# Photodiodes.net
KiCad netlist of a schematic drawn in Altium Designer
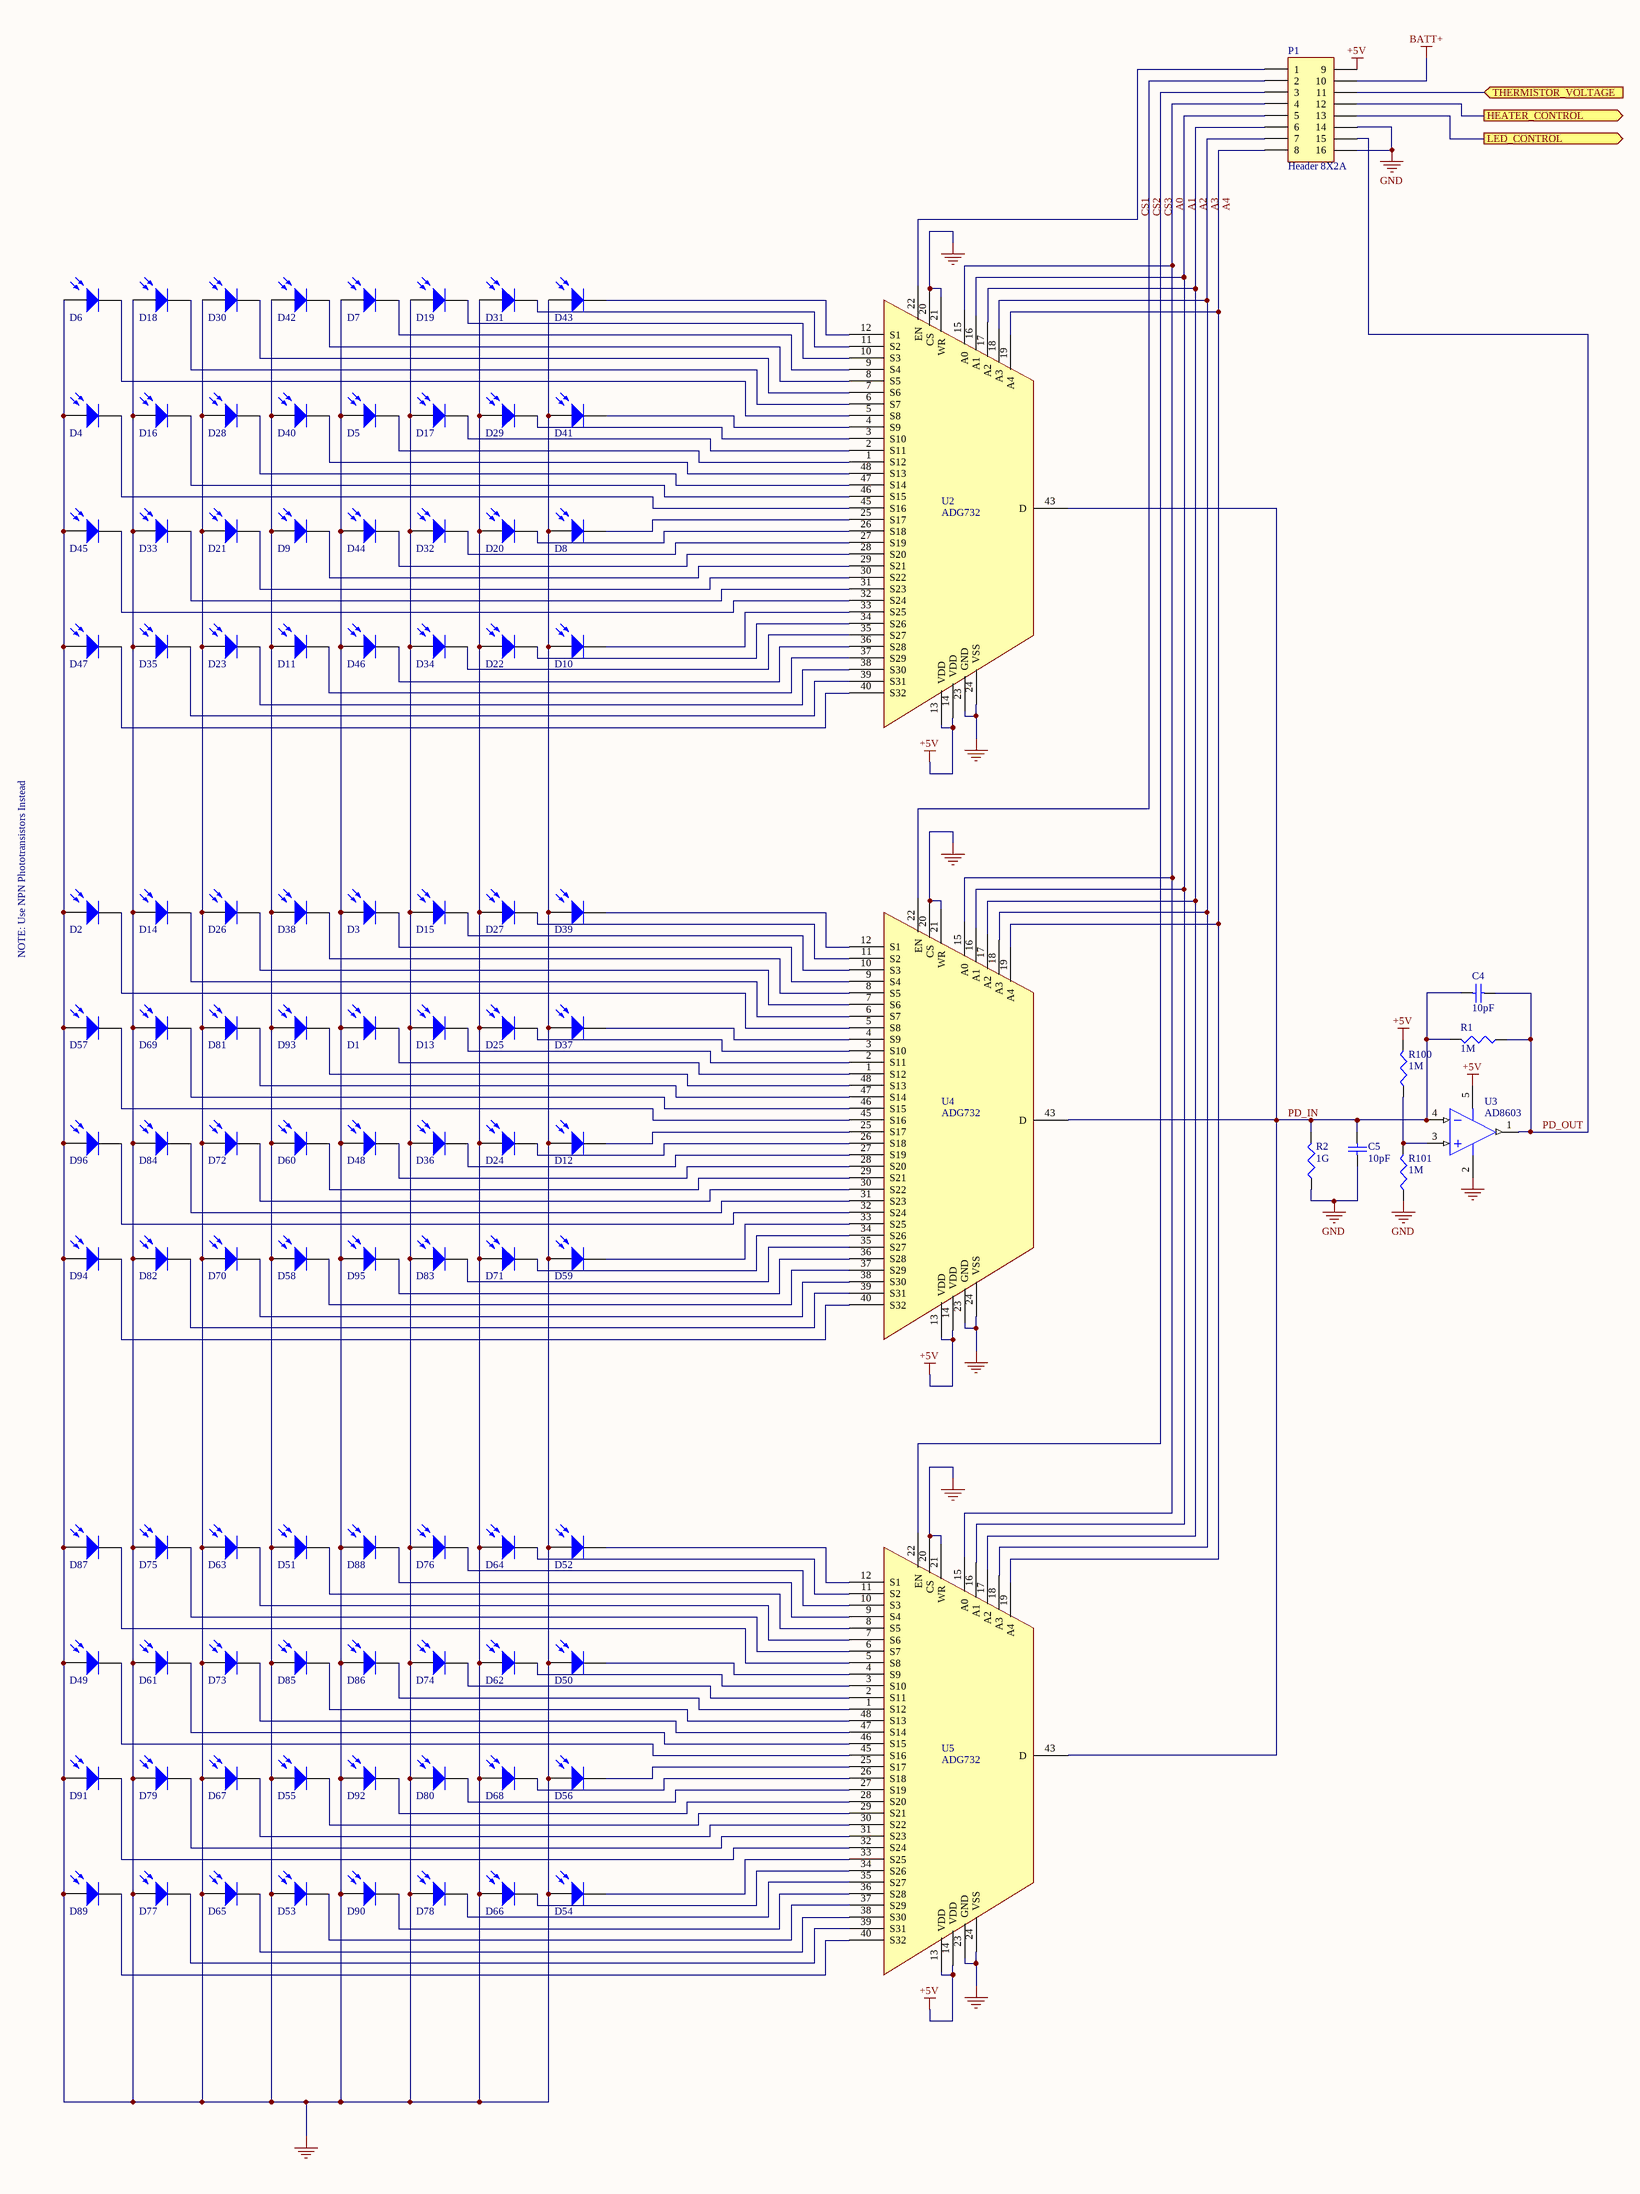
[diagram p0: Photodiodes.SchDoc]

(export (version "E")
  (design (tool "Eeschema 10.0.6"))
  (components
    (comp (ref "C4")
      (value "10pF")
      (footprint "CAPC3216L")
      (description "Capacitor (Semiconductor SIM Model)")
      (fields (field (name "Comment") "Cap Semi"))
      (libsource (lib "Miscellaneous Devices") (part "Cap Semi"))
    )
    (comp (ref "C5")
      (value "10pF")
      (footprint "CAPC3216L")
      (description "Capacitor (Semiconductor SIM Model)")
      (fields (field (name "Comment") "Cap Semi"))
      (libsource (lib "Miscellaneous Devices") (part "Cap Semi"))
    )
    (comp (ref "D1")
      (value "Photo Sen")
      (footprint "CAPC2012L")
      (description "Photosensitive Diode")
      (libsource (lib "Miscellaneous Devices") (part "Photo Sen"))
    )
    (comp (ref "D2")
      (value "Photo Sen")
      (footprint "CAPC2012L")
      (description "Photosensitive Diode")
      (libsource (lib "Miscellaneous Devices") (part "Photo Sen"))
    )
    (comp (ref "D3")
      (value "Photo Sen")
      (footprint "CAPC2012L")
      (description "Photosensitive Diode")
      (libsource (lib "Miscellaneous Devices") (part "Photo Sen"))
    )
    (comp (ref "D4")
      (value "Photo Sen")
      (footprint "CAPC2012L")
      (description "Photosensitive Diode")
      (libsource (lib "Miscellaneous Devices") (part "Photo Sen"))
    )
    (comp (ref "D5")
      (value "Photo Sen")
      (footprint "CAPC2012L")
      (description "Photosensitive Diode")
      (libsource (lib "Miscellaneous Devices") (part "Photo Sen"))
    )
    (comp (ref "D6")
      (value "Photo Sen")
      (footprint "CAPC2012L")
      (description "Photosensitive Diode")
      (libsource (lib "Miscellaneous Devices") (part "Photo Sen"))
    )
    (comp (ref "D7")
      (value "Photo Sen")
      (footprint "CAPC2012L")
      (description "Photosensitive Diode")
      (libsource (lib "Miscellaneous Devices") (part "Photo Sen"))
    )
    (comp (ref "D8")
      (value "Photo Sen")
      (footprint "CAPC2012L")
      (description "Photosensitive Diode")
      (libsource (lib "Miscellaneous Devices") (part "Photo Sen"))
    )
    (comp (ref "D9")
      (value "Photo Sen")
      (footprint "CAPC2012L")
      (description "Photosensitive Diode")
      (libsource (lib "Miscellaneous Devices") (part "Photo Sen"))
    )
    (comp (ref "D10")
      (value "Photo Sen")
      (footprint "CAPC2012L")
      (description "Photosensitive Diode")
      (libsource (lib "Miscellaneous Devices") (part "Photo Sen"))
    )
    (comp (ref "D11")
      (value "Photo Sen")
      (footprint "CAPC2012L")
      (description "Photosensitive Diode")
      (libsource (lib "Miscellaneous Devices") (part "Photo Sen"))
    )
    (comp (ref "D12")
      (value "Photo Sen")
      (footprint "CAPC2012L")
      (description "Photosensitive Diode")
      (libsource (lib "Miscellaneous Devices") (part "Photo Sen"))
    )
    (comp (ref "D13")
      (value "Photo Sen")
      (footprint "CAPC2012L")
      (description "Photosensitive Diode")
      (libsource (lib "Miscellaneous Devices") (part "Photo Sen"))
    )
    (comp (ref "D14")
      (value "Photo Sen")
      (footprint "CAPC2012L")
      (description "Photosensitive Diode")
      (libsource (lib "Miscellaneous Devices") (part "Photo Sen"))
    )
    (comp (ref "D15")
      (value "Photo Sen")
      (footprint "CAPC2012L")
      (description "Photosensitive Diode")
      (libsource (lib "Miscellaneous Devices") (part "Photo Sen"))
    )
    (comp (ref "D16")
      (value "Photo Sen")
      (footprint "CAPC2012L")
      (description "Photosensitive Diode")
      (libsource (lib "Miscellaneous Devices") (part "Photo Sen"))
    )
    (comp (ref "D17")
      (value "Photo Sen")
      (footprint "CAPC2012L")
      (description "Photosensitive Diode")
      (libsource (lib "Miscellaneous Devices") (part "Photo Sen"))
    )
    (comp (ref "D18")
      (value "Photo Sen")
      (footprint "CAPC2012L")
      (description "Photosensitive Diode")
      (libsource (lib "Miscellaneous Devices") (part "Photo Sen"))
    )
    (comp (ref "D19")
      (value "Photo Sen")
      (footprint "CAPC2012L")
      (description "Photosensitive Diode")
      (libsource (lib "Miscellaneous Devices") (part "Photo Sen"))
    )
    (comp (ref "D20")
      (value "Photo Sen")
      (footprint "CAPC2012L")
      (description "Photosensitive Diode")
      (libsource (lib "Miscellaneous Devices") (part "Photo Sen"))
    )
    (comp (ref "D21")
      (value "Photo Sen")
      (footprint "CAPC2012L")
      (description "Photosensitive Diode")
      (libsource (lib "Miscellaneous Devices") (part "Photo Sen"))
    )
    (comp (ref "D22")
      (value "Photo Sen")
      (footprint "CAPC2012L")
      (description "Photosensitive Diode")
      (libsource (lib "Miscellaneous Devices") (part "Photo Sen"))
    )
    (comp (ref "D23")
      (value "Photo Sen")
      (footprint "CAPC2012L")
      (description "Photosensitive Diode")
      (libsource (lib "Miscellaneous Devices") (part "Photo Sen"))
    )
    (comp (ref "D24")
      (value "Photo Sen")
      (footprint "CAPC2012L")
      (description "Photosensitive Diode")
      (libsource (lib "Miscellaneous Devices") (part "Photo Sen"))
    )
    (comp (ref "D25")
      (value "Photo Sen")
      (footprint "CAPC2012L")
      (description "Photosensitive Diode")
      (libsource (lib "Miscellaneous Devices") (part "Photo Sen"))
    )
    (comp (ref "D26")
      (value "Photo Sen")
      (footprint "CAPC2012L")
      (description "Photosensitive Diode")
      (libsource (lib "Miscellaneous Devices") (part "Photo Sen"))
    )
    (comp (ref "D27")
      (value "Photo Sen")
      (footprint "CAPC2012L")
      (description "Photosensitive Diode")
      (libsource (lib "Miscellaneous Devices") (part "Photo Sen"))
    )
    (comp (ref "D28")
      (value "Photo Sen")
      (footprint "CAPC2012L")
      (description "Photosensitive Diode")
      (libsource (lib "Miscellaneous Devices") (part "Photo Sen"))
    )
    (comp (ref "D29")
      (value "Photo Sen")
      (footprint "CAPC2012L")
      (description "Photosensitive Diode")
      (libsource (lib "Miscellaneous Devices") (part "Photo Sen"))
    )
    (comp (ref "D30")
      (value "Photo Sen")
      (footprint "CAPC2012L")
      (description "Photosensitive Diode")
      (libsource (lib "Miscellaneous Devices") (part "Photo Sen"))
    )
    (comp (ref "D31")
      (value "Photo Sen")
      (footprint "CAPC2012L")
      (description "Photosensitive Diode")
      (libsource (lib "Miscellaneous Devices") (part "Photo Sen"))
    )
    (comp (ref "D32")
      (value "Photo Sen")
      (footprint "CAPC2012L")
      (description "Photosensitive Diode")
      (libsource (lib "Miscellaneous Devices") (part "Photo Sen"))
    )
    (comp (ref "D33")
      (value "Photo Sen")
      (footprint "CAPC2012L")
      (description "Photosensitive Diode")
      (libsource (lib "Miscellaneous Devices") (part "Photo Sen"))
    )
    (comp (ref "D34")
      (value "Photo Sen")
      (footprint "CAPC2012L")
      (description "Photosensitive Diode")
      (libsource (lib "Miscellaneous Devices") (part "Photo Sen"))
    )
    (comp (ref "D35")
      (value "Photo Sen")
      (footprint "CAPC2012L")
      (description "Photosensitive Diode")
      (libsource (lib "Miscellaneous Devices") (part "Photo Sen"))
    )
    (comp (ref "D36")
      (value "Photo Sen")
      (footprint "CAPC2012L")
      (description "Photosensitive Diode")
      (libsource (lib "Miscellaneous Devices") (part "Photo Sen"))
    )
    (comp (ref "D37")
      (value "Photo Sen")
      (footprint "CAPC2012L")
      (description "Photosensitive Diode")
      (libsource (lib "Miscellaneous Devices") (part "Photo Sen"))
    )
    (comp (ref "D38")
      (value "Photo Sen")
      (footprint "CAPC2012L")
      (description "Photosensitive Diode")
      (libsource (lib "Miscellaneous Devices") (part "Photo Sen"))
    )
    (comp (ref "D39")
      (value "Photo Sen")
      (footprint "CAPC2012L")
      (description "Photosensitive Diode")
      (libsource (lib "Miscellaneous Devices") (part "Photo Sen"))
    )
    (comp (ref "D40")
      (value "Photo Sen")
      (footprint "CAPC2012L")
      (description "Photosensitive Diode")
      (libsource (lib "Miscellaneous Devices") (part "Photo Sen"))
    )
    (comp (ref "D41")
      (value "Photo Sen")
      (footprint "CAPC2012L")
      (description "Photosensitive Diode")
      (libsource (lib "Miscellaneous Devices") (part "Photo Sen"))
    )
    (comp (ref "D42")
      (value "Photo Sen")
      (footprint "CAPC2012L")
      (description "Photosensitive Diode")
      (libsource (lib "Miscellaneous Devices") (part "Photo Sen"))
    )
    (comp (ref "D43")
      (value "Photo Sen")
      (footprint "CAPC2012L")
      (description "Photosensitive Diode")
      (libsource (lib "Miscellaneous Devices") (part "Photo Sen"))
    )
    (comp (ref "D44")
      (value "Photo Sen")
      (footprint "CAPC2012L")
      (description "Photosensitive Diode")
      (libsource (lib "Miscellaneous Devices") (part "Photo Sen"))
    )
    (comp (ref "D45")
      (value "Photo Sen")
      (footprint "CAPC2012L")
      (description "Photosensitive Diode")
      (libsource (lib "Miscellaneous Devices") (part "Photo Sen"))
    )
    (comp (ref "D46")
      (value "Photo Sen")
      (footprint "CAPC2012L")
      (description "Photosensitive Diode")
      (libsource (lib "Miscellaneous Devices") (part "Photo Sen"))
    )
    (comp (ref "D47")
      (value "Photo Sen")
      (footprint "CAPC2012L")
      (description "Photosensitive Diode")
      (libsource (lib "Miscellaneous Devices") (part "Photo Sen"))
    )
    (comp (ref "D48")
      (value "Photo Sen")
      (footprint "CAPC2012L")
      (description "Photosensitive Diode")
      (libsource (lib "Miscellaneous Devices") (part "Photo Sen"))
    )
    (comp (ref "D49")
      (value "Photo Sen")
      (footprint "CAPC2012L")
      (description "Photosensitive Diode")
      (libsource (lib "Miscellaneous Devices") (part "Photo Sen"))
    )
    (comp (ref "D50")
      (value "Photo Sen")
      (footprint "CAPC2012L")
      (description "Photosensitive Diode")
      (libsource (lib "Miscellaneous Devices") (part "Photo Sen"))
    )
    (comp (ref "D51")
      (value "Photo Sen")
      (footprint "CAPC2012L")
      (description "Photosensitive Diode")
      (libsource (lib "Miscellaneous Devices") (part "Photo Sen"))
    )
    (comp (ref "D52")
      (value "Photo Sen")
      (footprint "CAPC2012L")
      (description "Photosensitive Diode")
      (libsource (lib "Miscellaneous Devices") (part "Photo Sen"))
    )
    (comp (ref "D53")
      (value "Photo Sen")
      (footprint "CAPC2012L")
      (description "Photosensitive Diode")
      (libsource (lib "Miscellaneous Devices") (part "Photo Sen"))
    )
    (comp (ref "D54")
      (value "Photo Sen")
      (footprint "CAPC2012L")
      (description "Photosensitive Diode")
      (libsource (lib "Miscellaneous Devices") (part "Photo Sen"))
    )
    (comp (ref "D55")
      (value "Photo Sen")
      (footprint "CAPC2012L")
      (description "Photosensitive Diode")
      (libsource (lib "Miscellaneous Devices") (part "Photo Sen"))
    )
    (comp (ref "D56")
      (value "Photo Sen")
      (footprint "CAPC2012L")
      (description "Photosensitive Diode")
      (libsource (lib "Miscellaneous Devices") (part "Photo Sen"))
    )
    (comp (ref "D57")
      (value "Photo Sen")
      (footprint "CAPC2012L")
      (description "Photosensitive Diode")
      (libsource (lib "Miscellaneous Devices") (part "Photo Sen"))
    )
    (comp (ref "D58")
      (value "Photo Sen")
      (footprint "CAPC2012L")
      (description "Photosensitive Diode")
      (libsource (lib "Miscellaneous Devices") (part "Photo Sen"))
    )
    (comp (ref "D59")
      (value "Photo Sen")
      (footprint "CAPC2012L")
      (description "Photosensitive Diode")
      (libsource (lib "Miscellaneous Devices") (part "Photo Sen"))
    )
    (comp (ref "D60")
      (value "Photo Sen")
      (footprint "CAPC2012L")
      (description "Photosensitive Diode")
      (libsource (lib "Miscellaneous Devices") (part "Photo Sen"))
    )
    (comp (ref "D61")
      (value "Photo Sen")
      (footprint "CAPC2012L")
      (description "Photosensitive Diode")
      (libsource (lib "Miscellaneous Devices") (part "Photo Sen"))
    )
    (comp (ref "D62")
      (value "Photo Sen")
      (footprint "CAPC2012L")
      (description "Photosensitive Diode")
      (libsource (lib "Miscellaneous Devices") (part "Photo Sen"))
    )
    (comp (ref "D63")
      (value "Photo Sen")
      (footprint "CAPC2012L")
      (description "Photosensitive Diode")
      (libsource (lib "Miscellaneous Devices") (part "Photo Sen"))
    )
    (comp (ref "D64")
      (value "Photo Sen")
      (footprint "CAPC2012L")
      (description "Photosensitive Diode")
      (libsource (lib "Miscellaneous Devices") (part "Photo Sen"))
    )
    (comp (ref "D65")
      (value "Photo Sen")
      (footprint "CAPC2012L")
      (description "Photosensitive Diode")
      (libsource (lib "Miscellaneous Devices") (part "Photo Sen"))
    )
    (comp (ref "D66")
      (value "Photo Sen")
      (footprint "CAPC2012L")
      (description "Photosensitive Diode")
      (libsource (lib "Miscellaneous Devices") (part "Photo Sen"))
    )
    (comp (ref "D67")
      (value "Photo Sen")
      (footprint "CAPC2012L")
      (description "Photosensitive Diode")
      (libsource (lib "Miscellaneous Devices") (part "Photo Sen"))
    )
    (comp (ref "D68")
      (value "Photo Sen")
      (footprint "CAPC2012L")
      (description "Photosensitive Diode")
      (libsource (lib "Miscellaneous Devices") (part "Photo Sen"))
    )
    (comp (ref "D69")
      (value "Photo Sen")
      (footprint "CAPC2012L")
      (description "Photosensitive Diode")
      (libsource (lib "Miscellaneous Devices") (part "Photo Sen"))
    )
    (comp (ref "D70")
      (value "Photo Sen")
      (footprint "CAPC2012L")
      (description "Photosensitive Diode")
      (libsource (lib "Miscellaneous Devices") (part "Photo Sen"))
    )
    (comp (ref "D71")
      (value "Photo Sen")
      (footprint "CAPC2012L")
      (description "Photosensitive Diode")
      (libsource (lib "Miscellaneous Devices") (part "Photo Sen"))
    )
    (comp (ref "D72")
      (value "Photo Sen")
      (footprint "CAPC2012L")
      (description "Photosensitive Diode")
      (libsource (lib "Miscellaneous Devices") (part "Photo Sen"))
    )
    (comp (ref "D73")
      (value "Photo Sen")
      (footprint "CAPC2012L")
      (description "Photosensitive Diode")
      (libsource (lib "Miscellaneous Devices") (part "Photo Sen"))
    )
    (comp (ref "D74")
      (value "Photo Sen")
      (footprint "CAPC2012L")
      (description "Photosensitive Diode")
      (libsource (lib "Miscellaneous Devices") (part "Photo Sen"))
    )
    (comp (ref "D75")
      (value "Photo Sen")
      (footprint "CAPC2012L")
      (description "Photosensitive Diode")
      (libsource (lib "Miscellaneous Devices") (part "Photo Sen"))
    )
    (comp (ref "D76")
      (value "Photo Sen")
      (footprint "CAPC2012L")
      (description "Photosensitive Diode")
      (libsource (lib "Miscellaneous Devices") (part "Photo Sen"))
    )
    (comp (ref "D77")
      (value "Photo Sen")
      (footprint "CAPC2012L")
      (description "Photosensitive Diode")
      (libsource (lib "Miscellaneous Devices") (part "Photo Sen"))
    )
    (comp (ref "D78")
      (value "Photo Sen")
      (footprint "CAPC2012L")
      (description "Photosensitive Diode")
      (libsource (lib "Miscellaneous Devices") (part "Photo Sen"))
    )
    (comp (ref "D79")
      (value "Photo Sen")
      (footprint "CAPC2012L")
      (description "Photosensitive Diode")
      (libsource (lib "Miscellaneous Devices") (part "Photo Sen"))
    )
    (comp (ref "D80")
      (value "Photo Sen")
      (footprint "CAPC2012L")
      (description "Photosensitive Diode")
      (libsource (lib "Miscellaneous Devices") (part "Photo Sen"))
    )
    (comp (ref "D81")
      (value "Photo Sen")
      (footprint "CAPC2012L")
      (description "Photosensitive Diode")
      (libsource (lib "Miscellaneous Devices") (part "Photo Sen"))
    )
    (comp (ref "D82")
      (value "Photo Sen")
      (footprint "CAPC2012L")
      (description "Photosensitive Diode")
      (libsource (lib "Miscellaneous Devices") (part "Photo Sen"))
    )
    (comp (ref "D83")
      (value "Photo Sen")
      (footprint "CAPC2012L")
      (description "Photosensitive Diode")
      (libsource (lib "Miscellaneous Devices") (part "Photo Sen"))
    )
    (comp (ref "D84")
      (value "Photo Sen")
      (footprint "CAPC2012L")
      (description "Photosensitive Diode")
      (libsource (lib "Miscellaneous Devices") (part "Photo Sen"))
    )
    (comp (ref "D85")
      (value "Photo Sen")
      (footprint "CAPC2012L")
      (description "Photosensitive Diode")
      (libsource (lib "Miscellaneous Devices") (part "Photo Sen"))
    )
    (comp (ref "D86")
      (value "Photo Sen")
      (footprint "CAPC2012L")
      (description "Photosensitive Diode")
      (libsource (lib "Miscellaneous Devices") (part "Photo Sen"))
    )
    (comp (ref "D87")
      (value "Photo Sen")
      (footprint "CAPC2012L")
      (description "Photosensitive Diode")
      (libsource (lib "Miscellaneous Devices") (part "Photo Sen"))
    )
    (comp (ref "D88")
      (value "Photo Sen")
      (footprint "CAPC2012L")
      (description "Photosensitive Diode")
      (libsource (lib "Miscellaneous Devices") (part "Photo Sen"))
    )
    (comp (ref "D89")
      (value "Photo Sen")
      (footprint "CAPC2012L")
      (description "Photosensitive Diode")
      (libsource (lib "Miscellaneous Devices") (part "Photo Sen"))
    )
    (comp (ref "D90")
      (value "Photo Sen")
      (footprint "CAPC2012L")
      (description "Photosensitive Diode")
      (libsource (lib "Miscellaneous Devices") (part "Photo Sen"))
    )
    (comp (ref "D91")
      (value "Photo Sen")
      (footprint "CAPC2012L")
      (description "Photosensitive Diode")
      (libsource (lib "Miscellaneous Devices") (part "Photo Sen"))
    )
    (comp (ref "D92")
      (value "Photo Sen")
      (footprint "CAPC2012L")
      (description "Photosensitive Diode")
      (libsource (lib "Miscellaneous Devices") (part "Photo Sen"))
    )
    (comp (ref "D93")
      (value "Photo Sen")
      (footprint "CAPC2012L")
      (description "Photosensitive Diode")
      (libsource (lib "Miscellaneous Devices") (part "Photo Sen"))
    )
    (comp (ref "D94")
      (value "Photo Sen")
      (footprint "CAPC2012L")
      (description "Photosensitive Diode")
      (libsource (lib "Miscellaneous Devices") (part "Photo Sen"))
    )
    (comp (ref "D95")
      (value "Photo Sen")
      (footprint "CAPC2012L")
      (description "Photosensitive Diode")
      (libsource (lib "Miscellaneous Devices") (part "Photo Sen"))
    )
    (comp (ref "D96")
      (value "Photo Sen")
      (footprint "CAPC2012L")
      (description "Photosensitive Diode")
      (libsource (lib "Miscellaneous Devices") (part "Photo Sen"))
    )
    (comp (ref "P1")
      (value "Header 8X2A")
      (footprint "HDR2X8_CEN")
      (description "Header, 8-Pin, Dual row")
      (libsource (lib "Miscellaneous Connectors") (part "Header 8X2A"))
    )
    (comp (ref "R1")
      (value "1M")
      (footprint "RESC3216L")
      (description "Resistor")
      (fields (field (name "Comment") "Res3"))
      (libsource (lib "Miscellaneous Devices") (part "Res3"))
    )
    (comp (ref "R2")
      (value "1G")
      (footprint "RESC3216L")
      (description "Resistor")
      (fields (field (name "Comment") "Res3"))
      (libsource (lib "Miscellaneous Devices") (part "Res3"))
    )
    (comp (ref "R100")
      (value "1M")
      (footprint "RESC3216L")
      (description "Resistor")
      (fields (field (name "Comment") "Res3"))
      (libsource (lib "Miscellaneous Devices") (part "Res3"))
    )
    (comp (ref "R101")
      (value "1M")
      (footprint "RESC3216L")
      (description "Resistor")
      (fields (field (name "Comment") "Res3"))
      (libsource (lib "Miscellaneous Devices") (part "Res3"))
    )
    (comp (ref "U2")
      (value "ADG732")
      (footprint "ST-48_M")
      (fields (field (name "SUPPLIER PART NUMBER 1") "ADG732BSUZ-ND"))
      (libsource (lib "Altium Footprints") (part "ADG732"))
    )
    (comp (ref "U3")
      (value "AD8603")
      (footprint "RJ-5")
      (description "Low Cost, Single, High-Speed Rail-to-Rail Amplifier")
      (libsource (lib "AD Operational Amplifier") (part "AD8051ART"))
    )
    (comp (ref "U4")
      (value "ADG732")
      (footprint "ST-48_M")
      (fields (field (name "SUPPLIER PART NUMBER 1") "ADG732BSUZ-ND"))
      (libsource (lib "Altium Footprints") (part "ADG732"))
    )
    (comp (ref "U5")
      (value "ADG732")
      (footprint "ST-48_M")
      (fields (field (name "SUPPLIER PART NUMBER 1") "ADG732BSUZ-ND"))
      (libsource (lib "Altium Footprints") (part "ADG732"))
    )
  )
  (nets
    (net (code "1") (name "+5V") (class "Default")
      (node (ref "P1") (pin "9") (pinfunction "9_9") (pintype "passive"))
      (node (ref "R100") (pin "2") (pinfunction "2_2") (pintype "passive"))
      (node (ref "U2") (pin "13") (pinfunction "VDD_13") (pintype "passive"))
      (node (ref "U2") (pin "14") (pinfunction "VDD_14") (pintype "passive"))
      (node (ref "U3") (pin "5") (pinfunction "V+_5") (pintype "power_in"))
      (node (ref "U4") (pin "13") (pinfunction "VDD_13") (pintype "passive"))
      (node (ref "U4") (pin "14") (pinfunction "VDD_14") (pintype "passive"))
      (node (ref "U5") (pin "13") (pinfunction "VDD_13") (pintype "passive"))
      (node (ref "U5") (pin "14") (pinfunction "VDD_14") (pintype "passive"))
    )
    (net (code "2") (name "/A0") (class "Default")
      (node (ref "P1") (pin "4") (pinfunction "4_4") (pintype "passive"))
      (node (ref "U2") (pin "15") (pinfunction "A0_15") (pintype "passive"))
      (node (ref "U4") (pin "15") (pinfunction "A0_15") (pintype "passive"))
      (node (ref "U5") (pin "15") (pinfunction "A0_15") (pintype "passive"))
    )
    (net (code "3") (name "/A1") (class "Default")
      (node (ref "P1") (pin "5") (pinfunction "5_5") (pintype "passive"))
      (node (ref "U2") (pin "16") (pinfunction "A1_16") (pintype "passive"))
      (node (ref "U4") (pin "16") (pinfunction "A1_16") (pintype "passive"))
      (node (ref "U5") (pin "16") (pinfunction "A1_16") (pintype "passive"))
    )
    (net (code "4") (name "/A2") (class "Default")
      (node (ref "P1") (pin "6") (pinfunction "6_6") (pintype "passive"))
      (node (ref "U2") (pin "17") (pinfunction "A2_17") (pintype "passive"))
      (node (ref "U4") (pin "17") (pinfunction "A2_17") (pintype "passive"))
      (node (ref "U5") (pin "17") (pinfunction "A2_17") (pintype "passive"))
    )
    (net (code "5") (name "/A3") (class "Default")
      (node (ref "P1") (pin "7") (pinfunction "7_7") (pintype "passive"))
      (node (ref "U2") (pin "18") (pinfunction "A3_18") (pintype "passive"))
      (node (ref "U4") (pin "18") (pinfunction "A3_18") (pintype "passive"))
      (node (ref "U5") (pin "18") (pinfunction "A3_18") (pintype "passive"))
    )
    (net (code "6") (name "/A4") (class "Default")
      (node (ref "P1") (pin "8") (pinfunction "8_8") (pintype "passive"))
      (node (ref "U2") (pin "19") (pinfunction "A4_19") (pintype "passive"))
      (node (ref "U4") (pin "19") (pinfunction "A4_19") (pintype "passive"))
      (node (ref "U5") (pin "19") (pinfunction "A4_19") (pintype "passive"))
    )
    (net (code "7") (name "/CS1") (class "Default")
      (node (ref "P1") (pin "1") (pinfunction "1_1") (pintype "passive"))
      (node (ref "U2") (pin "22") (pinfunction "EN_22") (pintype "passive"))
    )
    (net (code "8") (name "/CS2") (class "Default")
      (node (ref "P1") (pin "2") (pinfunction "2_2") (pintype "passive"))
      (node (ref "U4") (pin "22") (pinfunction "EN_22") (pintype "passive"))
    )
    (net (code "9") (name "/CS3") (class "Default")
      (node (ref "P1") (pin "3") (pinfunction "3_3") (pintype "passive"))
      (node (ref "U5") (pin "22") (pinfunction "EN_22") (pintype "passive"))
    )
    (net (code "10") (name "/HEATER_CONTROL") (class "Default")
      (node (ref "P1") (pin "12") (pinfunction "12_12") (pintype "passive"))
    )
    (net (code "11") (name "/LED_CONTROL") (class "Default")
      (node (ref "P1") (pin "13") (pinfunction "13_13") (pintype "passive"))
    )
    (net (code "12") (name "/PD_IN") (class "Default")
      (node (ref "C4") (pin "1") (pinfunction "1_1") (pintype "passive"))
      (node (ref "C5") (pin "2") (pinfunction "2_2") (pintype "passive"))
      (node (ref "R1") (pin "2") (pinfunction "2_2") (pintype "passive"))
      (node (ref "R2") (pin "2") (pinfunction "2_2") (pintype "passive"))
      (node (ref "U2") (pin "43") (pinfunction "D_43") (pintype "passive"))
      (node (ref "U3") (pin "4") (pinfunction "IN-_4") (pintype "input"))
      (node (ref "U4") (pin "43") (pinfunction "D_43") (pintype "passive"))
      (node (ref "U5") (pin "43") (pinfunction "D_43") (pintype "passive"))
    )
    (net (code "13") (name "/PD_OUT") (class "Default")
      (node (ref "C4") (pin "2") (pinfunction "2_2") (pintype "passive"))
      (node (ref "P1") (pin "15") (pinfunction "15_15") (pintype "passive"))
      (node (ref "R1") (pin "1") (pinfunction "1_1") (pintype "passive"))
      (node (ref "U3") (pin "1") (pinfunction "OUT_1") (pintype "output"))
    )
    (net (code "14") (name "/THERMISTOR_VOLTAGE") (class "Default")
      (node (ref "P1") (pin "11") (pinfunction "11_11") (pintype "passive"))
    )
    (net (code "15") (name "BATT+") (class "Default")
      (node (ref "P1") (pin "10") (pinfunction "10_10") (pintype "passive"))
    )
    (net (code "16") (name "GND") (class "Default")
      (node (ref "C5") (pin "1") (pinfunction "1_1") (pintype "passive"))
      (node (ref "D1") (pin "1") (pinfunction "A_1") (pintype "passive"))
      (node (ref "D10") (pin "1") (pinfunction "A_1") (pintype "passive"))
      (node (ref "D11") (pin "1") (pinfunction "A_1") (pintype "passive"))
      (node (ref "D12") (pin "1") (pinfunction "A_1") (pintype "passive"))
      (node (ref "D13") (pin "1") (pinfunction "A_1") (pintype "passive"))
      (node (ref "D14") (pin "1") (pinfunction "A_1") (pintype "passive"))
      (node (ref "D15") (pin "1") (pinfunction "A_1") (pintype "passive"))
      (node (ref "D16") (pin "1") (pinfunction "A_1") (pintype "passive"))
      (node (ref "D17") (pin "1") (pinfunction "A_1") (pintype "passive"))
      (node (ref "D18") (pin "1") (pinfunction "A_1") (pintype "passive"))
      (node (ref "D19") (pin "1") (pinfunction "A_1") (pintype "passive"))
      (node (ref "D2") (pin "1") (pinfunction "A_1") (pintype "passive"))
      (node (ref "D20") (pin "1") (pinfunction "A_1") (pintype "passive"))
      (node (ref "D21") (pin "1") (pinfunction "A_1") (pintype "passive"))
      (node (ref "D22") (pin "1") (pinfunction "A_1") (pintype "passive"))
      (node (ref "D23") (pin "1") (pinfunction "A_1") (pintype "passive"))
      (node (ref "D24") (pin "1") (pinfunction "A_1") (pintype "passive"))
      (node (ref "D25") (pin "1") (pinfunction "A_1") (pintype "passive"))
      (node (ref "D26") (pin "1") (pinfunction "A_1") (pintype "passive"))
      (node (ref "D27") (pin "1") (pinfunction "A_1") (pintype "passive"))
      (node (ref "D28") (pin "1") (pinfunction "A_1") (pintype "passive"))
      (node (ref "D29") (pin "1") (pinfunction "A_1") (pintype "passive"))
      (node (ref "D3") (pin "1") (pinfunction "A_1") (pintype "passive"))
      (node (ref "D30") (pin "1") (pinfunction "A_1") (pintype "passive"))
      (node (ref "D31") (pin "1") (pinfunction "A_1") (pintype "passive"))
      (node (ref "D32") (pin "1") (pinfunction "A_1") (pintype "passive"))
      (node (ref "D33") (pin "1") (pinfunction "A_1") (pintype "passive"))
      (node (ref "D34") (pin "1") (pinfunction "A_1") (pintype "passive"))
      (node (ref "D35") (pin "1") (pinfunction "A_1") (pintype "passive"))
      (node (ref "D36") (pin "1") (pinfunction "A_1") (pintype "passive"))
      (node (ref "D37") (pin "1") (pinfunction "A_1") (pintype "passive"))
      (node (ref "D38") (pin "1") (pinfunction "A_1") (pintype "passive"))
      (node (ref "D39") (pin "1") (pinfunction "A_1") (pintype "passive"))
      (node (ref "D4") (pin "1") (pinfunction "A_1") (pintype "passive"))
      (node (ref "D40") (pin "1") (pinfunction "A_1") (pintype "passive"))
      (node (ref "D41") (pin "1") (pinfunction "A_1") (pintype "passive"))
      (node (ref "D42") (pin "1") (pinfunction "A_1") (pintype "passive"))
      (node (ref "D43") (pin "1") (pinfunction "A_1") (pintype "passive"))
      (node (ref "D44") (pin "1") (pinfunction "A_1") (pintype "passive"))
      (node (ref "D45") (pin "1") (pinfunction "A_1") (pintype "passive"))
      (node (ref "D46") (pin "1") (pinfunction "A_1") (pintype "passive"))
      (node (ref "D47") (pin "1") (pinfunction "A_1") (pintype "passive"))
      (node (ref "D48") (pin "1") (pinfunction "A_1") (pintype "passive"))
      (node (ref "D49") (pin "1") (pinfunction "A_1") (pintype "passive"))
      (node (ref "D5") (pin "1") (pinfunction "A_1") (pintype "passive"))
      (node (ref "D50") (pin "1") (pinfunction "A_1") (pintype "passive"))
      (node (ref "D51") (pin "1") (pinfunction "A_1") (pintype "passive"))
      (node (ref "D52") (pin "1") (pinfunction "A_1") (pintype "passive"))
      (node (ref "D53") (pin "1") (pinfunction "A_1") (pintype "passive"))
      (node (ref "D54") (pin "1") (pinfunction "A_1") (pintype "passive"))
      (node (ref "D55") (pin "1") (pinfunction "A_1") (pintype "passive"))
      (node (ref "D56") (pin "1") (pinfunction "A_1") (pintype "passive"))
      (node (ref "D57") (pin "1") (pinfunction "A_1") (pintype "passive"))
      (node (ref "D58") (pin "1") (pinfunction "A_1") (pintype "passive"))
      (node (ref "D59") (pin "1") (pinfunction "A_1") (pintype "passive"))
      (node (ref "D6") (pin "1") (pinfunction "A_1") (pintype "passive"))
      (node (ref "D60") (pin "1") (pinfunction "A_1") (pintype "passive"))
      (node (ref "D61") (pin "1") (pinfunction "A_1") (pintype "passive"))
      (node (ref "D62") (pin "1") (pinfunction "A_1") (pintype "passive"))
      (node (ref "D63") (pin "1") (pinfunction "A_1") (pintype "passive"))
      (node (ref "D64") (pin "1") (pinfunction "A_1") (pintype "passive"))
      (node (ref "D65") (pin "1") (pinfunction "A_1") (pintype "passive"))
      (node (ref "D66") (pin "1") (pinfunction "A_1") (pintype "passive"))
      (node (ref "D67") (pin "1") (pinfunction "A_1") (pintype "passive"))
      (node (ref "D68") (pin "1") (pinfunction "A_1") (pintype "passive"))
      (node (ref "D69") (pin "1") (pinfunction "A_1") (pintype "passive"))
      (node (ref "D7") (pin "1") (pinfunction "A_1") (pintype "passive"))
      (node (ref "D70") (pin "1") (pinfunction "A_1") (pintype "passive"))
      (node (ref "D71") (pin "1") (pinfunction "A_1") (pintype "passive"))
      (node (ref "D72") (pin "1") (pinfunction "A_1") (pintype "passive"))
      (node (ref "D73") (pin "1") (pinfunction "A_1") (pintype "passive"))
      (node (ref "D74") (pin "1") (pinfunction "A_1") (pintype "passive"))
      (node (ref "D75") (pin "1") (pinfunction "A_1") (pintype "passive"))
      (node (ref "D76") (pin "1") (pinfunction "A_1") (pintype "passive"))
      (node (ref "D77") (pin "1") (pinfunction "A_1") (pintype "passive"))
      (node (ref "D78") (pin "1") (pinfunction "A_1") (pintype "passive"))
      (node (ref "D79") (pin "1") (pinfunction "A_1") (pintype "passive"))
      (node (ref "D8") (pin "1") (pinfunction "A_1") (pintype "passive"))
      (node (ref "D80") (pin "1") (pinfunction "A_1") (pintype "passive"))
      (node (ref "D81") (pin "1") (pinfunction "A_1") (pintype "passive"))
      (node (ref "D82") (pin "1") (pinfunction "A_1") (pintype "passive"))
      (node (ref "D83") (pin "1") (pinfunction "A_1") (pintype "passive"))
      (node (ref "D84") (pin "1") (pinfunction "A_1") (pintype "passive"))
      (node (ref "D85") (pin "1") (pinfunction "A_1") (pintype "passive"))
      (node (ref "D86") (pin "1") (pinfunction "A_1") (pintype "passive"))
      (node (ref "D87") (pin "1") (pinfunction "A_1") (pintype "passive"))
      (node (ref "D88") (pin "1") (pinfunction "A_1") (pintype "passive"))
      (node (ref "D89") (pin "1") (pinfunction "A_1") (pintype "passive"))
      (node (ref "D9") (pin "1") (pinfunction "A_1") (pintype "passive"))
      (node (ref "D90") (pin "1") (pinfunction "A_1") (pintype "passive"))
      (node (ref "D91") (pin "1") (pinfunction "A_1") (pintype "passive"))
      (node (ref "D92") (pin "1") (pinfunction "A_1") (pintype "passive"))
      (node (ref "D93") (pin "1") (pinfunction "A_1") (pintype "passive"))
      (node (ref "D94") (pin "1") (pinfunction "A_1") (pintype "passive"))
      (node (ref "D95") (pin "1") (pinfunction "A_1") (pintype "passive"))
      (node (ref "D96") (pin "1") (pinfunction "A_1") (pintype "passive"))
      (node (ref "P1") (pin "14") (pinfunction "14_14") (pintype "passive"))
      (node (ref "P1") (pin "16") (pinfunction "16_16") (pintype "passive"))
      (node (ref "R101") (pin "1") (pinfunction "1_1") (pintype "passive"))
      (node (ref "R2") (pin "1") (pinfunction "1_1") (pintype "passive"))
      (node (ref "U2") (pin "20") (pinfunction "CS_20") (pintype "passive"))
      (node (ref "U2") (pin "21") (pinfunction "WR_21") (pintype "passive"))
      (node (ref "U2") (pin "23") (pinfunction "GND_23") (pintype "passive"))
      (node (ref "U2") (pin "24") (pinfunction "VSS_24") (pintype "passive"))
      (node (ref "U3") (pin "2") (pinfunction "V-_2") (pintype "power_in"))
      (node (ref "U4") (pin "20") (pinfunction "CS_20") (pintype "passive"))
      (node (ref "U4") (pin "21") (pinfunction "WR_21") (pintype "passive"))
      (node (ref "U4") (pin "23") (pinfunction "GND_23") (pintype "passive"))
      (node (ref "U4") (pin "24") (pinfunction "VSS_24") (pintype "passive"))
      (node (ref "U5") (pin "20") (pinfunction "CS_20") (pintype "passive"))
      (node (ref "U5") (pin "21") (pinfunction "WR_21") (pintype "passive"))
      (node (ref "U5") (pin "23") (pinfunction "GND_23") (pintype "passive"))
      (node (ref "U5") (pin "24") (pinfunction "VSS_24") (pintype "passive"))
    )
    (net (code "17") (name "Net-(D1-K)") (class "Default")
      (node (ref "D1") (pin "2") (pinfunction "K_2") (pintype "passive"))
      (node (ref "U4") (pin "1") (pinfunction "S12_1") (pintype "passive"))
    )
    (net (code "18") (name "Net-(D2-K)") (class "Default")
      (node (ref "D2") (pin "2") (pinfunction "K_2") (pintype "passive"))
      (node (ref "U4") (pin "5") (pinfunction "S8_5") (pintype "passive"))
    )
    (net (code "19") (name "Net-(D3-K)") (class "Default")
      (node (ref "D3") (pin "2") (pinfunction "K_2") (pintype "passive"))
      (node (ref "U4") (pin "9") (pinfunction "S4_9") (pintype "passive"))
    )
    (net (code "20") (name "Net-(D4-K)") (class "Default")
      (node (ref "D4") (pin "2") (pinfunction "K_2") (pintype "passive"))
      (node (ref "U2") (pin "45") (pinfunction "S16_45") (pintype "passive"))
    )
    (net (code "21") (name "Net-(D5-K)") (class "Default")
      (node (ref "D5") (pin "2") (pinfunction "K_2") (pintype "passive"))
      (node (ref "U2") (pin "1") (pinfunction "S12_1") (pintype "passive"))
    )
    (net (code "22") (name "Net-(D6-K)") (class "Default")
      (node (ref "D6") (pin "2") (pinfunction "K_2") (pintype "passive"))
      (node (ref "U2") (pin "5") (pinfunction "S8_5") (pintype "passive"))
    )
    (net (code "23") (name "Net-(D7-K)") (class "Default")
      (node (ref "D7") (pin "2") (pinfunction "K_2") (pintype "passive"))
      (node (ref "U2") (pin "9") (pinfunction "S4_9") (pintype "passive"))
    )
    (net (code "24") (name "Net-(D8-K)") (class "Default")
      (node (ref "D8") (pin "2") (pinfunction "K_2") (pintype "passive"))
      (node (ref "U2") (pin "25") (pinfunction "S17_25") (pintype "passive"))
    )
    (net (code "25") (name "Net-(D9-K)") (class "Default")
      (node (ref "D9") (pin "2") (pinfunction "K_2") (pintype "passive"))
      (node (ref "U2") (pin "29") (pinfunction "S21_29") (pintype "passive"))
    )
    (net (code "26") (name "Net-(D10-K)") (class "Default")
      (node (ref "D10") (pin "2") (pinfunction "K_2") (pintype "passive"))
      (node (ref "U2") (pin "33") (pinfunction "S25_33") (pintype "passive"))
    )
    (net (code "27") (name "Net-(D11-K)") (class "Default")
      (node (ref "D11") (pin "2") (pinfunction "K_2") (pintype "passive"))
      (node (ref "U2") (pin "37") (pinfunction "S29_37") (pintype "passive"))
    )
    (net (code "28") (name "Net-(D12-K)") (class "Default")
      (node (ref "D12") (pin "2") (pinfunction "K_2") (pintype "passive"))
      (node (ref "U4") (pin "25") (pinfunction "S17_25") (pintype "passive"))
    )
    (net (code "29") (name "Net-(D13-K)") (class "Default")
      (node (ref "D13") (pin "2") (pinfunction "K_2") (pintype "passive"))
      (node (ref "U4") (pin "2") (pinfunction "S11_2") (pintype "passive"))
    )
    (net (code "30") (name "Net-(D14-K)") (class "Default")
      (node (ref "D14") (pin "2") (pinfunction "K_2") (pintype "passive"))
      (node (ref "U4") (pin "6") (pinfunction "S7_6") (pintype "passive"))
    )
    (net (code "31") (name "Net-(D15-K)") (class "Default")
      (node (ref "D15") (pin "2") (pinfunction "K_2") (pintype "passive"))
      (node (ref "U4") (pin "10") (pinfunction "S3_10") (pintype "passive"))
    )
    (net (code "32") (name "Net-(D16-K)") (class "Default")
      (node (ref "D16") (pin "2") (pinfunction "K_2") (pintype "passive"))
      (node (ref "U2") (pin "46") (pinfunction "S15_46") (pintype "passive"))
    )
    (net (code "33") (name "Net-(D17-K)") (class "Default")
      (node (ref "D17") (pin "2") (pinfunction "K_2") (pintype "passive"))
      (node (ref "U2") (pin "2") (pinfunction "S11_2") (pintype "passive"))
    )
    (net (code "34") (name "Net-(D18-K)") (class "Default")
      (node (ref "D18") (pin "2") (pinfunction "K_2") (pintype "passive"))
      (node (ref "U2") (pin "6") (pinfunction "S7_6") (pintype "passive"))
    )
    (net (code "35") (name "Net-(D19-K)") (class "Default")
      (node (ref "D19") (pin "2") (pinfunction "K_2") (pintype "passive"))
      (node (ref "U2") (pin "10") (pinfunction "S3_10") (pintype "passive"))
    )
    (net (code "36") (name "Net-(D20-K)") (class "Default")
      (node (ref "D20") (pin "2") (pinfunction "K_2") (pintype "passive"))
      (node (ref "U2") (pin "26") (pinfunction "S18_26") (pintype "passive"))
    )
    (net (code "37") (name "Net-(D21-K)") (class "Default")
      (node (ref "D21") (pin "2") (pinfunction "K_2") (pintype "passive"))
      (node (ref "U2") (pin "30") (pinfunction "S22_30") (pintype "passive"))
    )
    (net (code "38") (name "Net-(D22-K)") (class "Default")
      (node (ref "D22") (pin "2") (pinfunction "K_2") (pintype "passive"))
      (node (ref "U2") (pin "34") (pinfunction "S26_34") (pintype "passive"))
    )
    (net (code "39") (name "Net-(D23-K)") (class "Default")
      (node (ref "D23") (pin "2") (pinfunction "K_2") (pintype "passive"))
      (node (ref "U2") (pin "38") (pinfunction "S30_38") (pintype "passive"))
    )
    (net (code "40") (name "Net-(D24-K)") (class "Default")
      (node (ref "D24") (pin "2") (pinfunction "K_2") (pintype "passive"))
      (node (ref "U4") (pin "26") (pinfunction "S18_26") (pintype "passive"))
    )
    (net (code "41") (name "Net-(D25-K)") (class "Default")
      (node (ref "D25") (pin "2") (pinfunction "K_2") (pintype "passive"))
      (node (ref "U4") (pin "3") (pinfunction "S10_3") (pintype "passive"))
    )
    (net (code "42") (name "Net-(D26-K)") (class "Default")
      (node (ref "D26") (pin "2") (pinfunction "K_2") (pintype "passive"))
      (node (ref "U4") (pin "7") (pinfunction "S6_7") (pintype "passive"))
    )
    (net (code "43") (name "Net-(D27-K)") (class "Default")
      (node (ref "D27") (pin "2") (pinfunction "K_2") (pintype "passive"))
      (node (ref "U4") (pin "11") (pinfunction "S2_11") (pintype "passive"))
    )
    (net (code "44") (name "Net-(D28-K)") (class "Default")
      (node (ref "D28") (pin "2") (pinfunction "K_2") (pintype "passive"))
      (node (ref "U2") (pin "47") (pinfunction "S14_47") (pintype "passive"))
    )
    (net (code "45") (name "Net-(D29-K)") (class "Default")
      (node (ref "D29") (pin "2") (pinfunction "K_2") (pintype "passive"))
      (node (ref "U2") (pin "3") (pinfunction "S10_3") (pintype "passive"))
    )
    (net (code "46") (name "Net-(D30-K)") (class "Default")
      (node (ref "D30") (pin "2") (pinfunction "K_2") (pintype "passive"))
      (node (ref "U2") (pin "7") (pinfunction "S6_7") (pintype "passive"))
    )
    (net (code "47") (name "Net-(D31-K)") (class "Default")
      (node (ref "D31") (pin "2") (pinfunction "K_2") (pintype "passive"))
      (node (ref "U2") (pin "11") (pinfunction "S2_11") (pintype "passive"))
    )
    (net (code "48") (name "Net-(D32-K)") (class "Default")
      (node (ref "D32") (pin "2") (pinfunction "K_2") (pintype "passive"))
      (node (ref "U2") (pin "27") (pinfunction "S19_27") (pintype "passive"))
    )
    (net (code "49") (name "Net-(D33-K)") (class "Default")
      (node (ref "D33") (pin "2") (pinfunction "K_2") (pintype "passive"))
      (node (ref "U2") (pin "31") (pinfunction "S23_31") (pintype "passive"))
    )
    (net (code "50") (name "Net-(D34-K)") (class "Default")
      (node (ref "D34") (pin "2") (pinfunction "K_2") (pintype "passive"))
      (node (ref "U2") (pin "35") (pinfunction "S27_35") (pintype "passive"))
    )
    (net (code "51") (name "Net-(D35-K)") (class "Default")
      (node (ref "D35") (pin "2") (pinfunction "K_2") (pintype "passive"))
      (node (ref "U2") (pin "39") (pinfunction "S31_39") (pintype "passive"))
    )
    (net (code "52") (name "Net-(D36-K)") (class "Default")
      (node (ref "D36") (pin "2") (pinfunction "K_2") (pintype "passive"))
      (node (ref "U4") (pin "27") (pinfunction "S19_27") (pintype "passive"))
    )
    (net (code "53") (name "Net-(D37-K)") (class "Default")
      (node (ref "D37") (pin "2") (pinfunction "K_2") (pintype "passive"))
      (node (ref "U4") (pin "4") (pinfunction "S9_4") (pintype "passive"))
    )
    (net (code "54") (name "Net-(D38-K)") (class "Default")
      (node (ref "D38") (pin "2") (pinfunction "K_2") (pintype "passive"))
      (node (ref "U4") (pin "8") (pinfunction "S5_8") (pintype "passive"))
    )
    (net (code "55") (name "Net-(D39-K)") (class "Default")
      (node (ref "D39") (pin "2") (pinfunction "K_2") (pintype "passive"))
      (node (ref "U4") (pin "12") (pinfunction "S1_12") (pintype "passive"))
    )
    (net (code "56") (name "Net-(D40-K)") (class "Default")
      (node (ref "D40") (pin "2") (pinfunction "K_2") (pintype "passive"))
      (node (ref "U2") (pin "48") (pinfunction "S13_48") (pintype "passive"))
    )
    (net (code "57") (name "Net-(D41-K)") (class "Default")
      (node (ref "D41") (pin "2") (pinfunction "K_2") (pintype "passive"))
      (node (ref "U2") (pin "4") (pinfunction "S9_4") (pintype "passive"))
    )
    (net (code "58") (name "Net-(D42-K)") (class "Default")
      (node (ref "D42") (pin "2") (pinfunction "K_2") (pintype "passive"))
      (node (ref "U2") (pin "8") (pinfunction "S5_8") (pintype "passive"))
    )
    (net (code "59") (name "Net-(D43-K)") (class "Default")
      (node (ref "D43") (pin "2") (pinfunction "K_2") (pintype "passive"))
      (node (ref "U2") (pin "12") (pinfunction "S1_12") (pintype "passive"))
    )
    (net (code "60") (name "Net-(D44-K)") (class "Default")
      (node (ref "D44") (pin "2") (pinfunction "K_2") (pintype "passive"))
      (node (ref "U2") (pin "28") (pinfunction "S20_28") (pintype "passive"))
    )
    (net (code "61") (name "Net-(D45-K)") (class "Default")
      (node (ref "D45") (pin "2") (pinfunction "K_2") (pintype "passive"))
      (node (ref "U2") (pin "32") (pinfunction "S24_32") (pintype "passive"))
    )
    (net (code "62") (name "Net-(D46-K)") (class "Default")
      (node (ref "D46") (pin "2") (pinfunction "K_2") (pintype "passive"))
      (node (ref "U2") (pin "36") (pinfunction "S28_36") (pintype "passive"))
    )
    (net (code "63") (name "Net-(D47-K)") (class "Default")
      (node (ref "D47") (pin "2") (pinfunction "K_2") (pintype "passive"))
      (node (ref "U2") (pin "40") (pinfunction "S32_40") (pintype "passive"))
    )
    (net (code "64") (name "Net-(D48-K)") (class "Default")
      (node (ref "D48") (pin "2") (pinfunction "K_2") (pintype "passive"))
      (node (ref "U4") (pin "28") (pinfunction "S20_28") (pintype "passive"))
    )
    (net (code "65") (name "Net-(D49-K)") (class "Default")
      (node (ref "D49") (pin "2") (pinfunction "K_2") (pintype "passive"))
      (node (ref "U5") (pin "45") (pinfunction "S16_45") (pintype "passive"))
    )
    (net (code "66") (name "Net-(D50-K)") (class "Default")
      (node (ref "D50") (pin "2") (pinfunction "K_2") (pintype "passive"))
      (node (ref "U5") (pin "4") (pinfunction "S9_4") (pintype "passive"))
    )
    (net (code "67") (name "Net-(D51-K)") (class "Default")
      (node (ref "D51") (pin "2") (pinfunction "K_2") (pintype "passive"))
      (node (ref "U5") (pin "8") (pinfunction "S5_8") (pintype "passive"))
    )
    (net (code "68") (name "Net-(D52-K)") (class "Default")
      (node (ref "D52") (pin "2") (pinfunction "K_2") (pintype "passive"))
      (node (ref "U5") (pin "12") (pinfunction "S1_12") (pintype "passive"))
    )
    (net (code "69") (name "Net-(D53-K)") (class "Default")
      (node (ref "D53") (pin "2") (pinfunction "K_2") (pintype "passive"))
      (node (ref "U5") (pin "37") (pinfunction "S29_37") (pintype "passive"))
    )
    (net (code "70") (name "Net-(D54-K)") (class "Default")
      (node (ref "D54") (pin "2") (pinfunction "K_2") (pintype "passive"))
      (node (ref "U5") (pin "33") (pinfunction "S25_33") (pintype "passive"))
    )
    (net (code "71") (name "Net-(D55-K)") (class "Default")
      (node (ref "D55") (pin "2") (pinfunction "K_2") (pintype "passive"))
      (node (ref "U5") (pin "29") (pinfunction "S21_29") (pintype "passive"))
    )
    (net (code "72") (name "Net-(D56-K)") (class "Default")
      (node (ref "D56") (pin "2") (pinfunction "K_2") (pintype "passive"))
      (node (ref "U5") (pin "25") (pinfunction "S17_25") (pintype "passive"))
    )
    (net (code "73") (name "Net-(D57-K)") (class "Default")
      (node (ref "D57") (pin "2") (pinfunction "K_2") (pintype "passive"))
      (node (ref "U4") (pin "45") (pinfunction "S16_45") (pintype "passive"))
    )
    (net (code "74") (name "Net-(D58-K)") (class "Default")
      (node (ref "D58") (pin "2") (pinfunction "K_2") (pintype "passive"))
      (node (ref "U4") (pin "37") (pinfunction "S29_37") (pintype "passive"))
    )
    (net (code "75") (name "Net-(D59-K)") (class "Default")
      (node (ref "D59") (pin "2") (pinfunction "K_2") (pintype "passive"))
      (node (ref "U4") (pin "33") (pinfunction "S25_33") (pintype "passive"))
    )
    (net (code "76") (name "Net-(D60-K)") (class "Default")
      (node (ref "D60") (pin "2") (pinfunction "K_2") (pintype "passive"))
      (node (ref "U4") (pin "29") (pinfunction "S21_29") (pintype "passive"))
    )
    (net (code "77") (name "Net-(D61-K)") (class "Default")
      (node (ref "D61") (pin "2") (pinfunction "K_2") (pintype "passive"))
      (node (ref "U5") (pin "46") (pinfunction "S15_46") (pintype "passive"))
    )
    (net (code "78") (name "Net-(D62-K)") (class "Default")
      (node (ref "D62") (pin "2") (pinfunction "K_2") (pintype "passive"))
      (node (ref "U5") (pin "3") (pinfunction "S10_3") (pintype "passive"))
    )
    (net (code "79") (name "Net-(D63-K)") (class "Default")
      (node (ref "D63") (pin "2") (pinfunction "K_2") (pintype "passive"))
      (node (ref "U5") (pin "7") (pinfunction "S6_7") (pintype "passive"))
    )
    (net (code "80") (name "Net-(D64-K)") (class "Default")
      (node (ref "D64") (pin "2") (pinfunction "K_2") (pintype "passive"))
      (node (ref "U5") (pin "11") (pinfunction "S2_11") (pintype "passive"))
    )
    (net (code "81") (name "Net-(D65-K)") (class "Default")
      (node (ref "D65") (pin "2") (pinfunction "K_2") (pintype "passive"))
      (node (ref "U5") (pin "38") (pinfunction "S30_38") (pintype "passive"))
    )
    (net (code "82") (name "Net-(D66-K)") (class "Default")
      (node (ref "D66") (pin "2") (pinfunction "K_2") (pintype "passive"))
      (node (ref "U5") (pin "34") (pinfunction "S26_34") (pintype "passive"))
    )
    (net (code "83") (name "Net-(D67-K)") (class "Default")
      (node (ref "D67") (pin "2") (pinfunction "K_2") (pintype "passive"))
      (node (ref "U5") (pin "30") (pinfunction "S22_30") (pintype "passive"))
    )
    (net (code "84") (name "Net-(D68-K)") (class "Default")
      (node (ref "D68") (pin "2") (pinfunction "K_2") (pintype "passive"))
      (node (ref "U5") (pin "26") (pinfunction "S18_26") (pintype "passive"))
    )
    (net (code "85") (name "Net-(D69-K)") (class "Default")
      (node (ref "D69") (pin "2") (pinfunction "K_2") (pintype "passive"))
      (node (ref "U4") (pin "46") (pinfunction "S15_46") (pintype "passive"))
    )
    (net (code "86") (name "Net-(D70-K)") (class "Default")
      (node (ref "D70") (pin "2") (pinfunction "K_2") (pintype "passive"))
      (node (ref "U4") (pin "38") (pinfunction "S30_38") (pintype "passive"))
    )
    (net (code "87") (name "Net-(D71-K)") (class "Default")
      (node (ref "D71") (pin "2") (pinfunction "K_2") (pintype "passive"))
      (node (ref "U4") (pin "34") (pinfunction "S26_34") (pintype "passive"))
    )
    (net (code "88") (name "Net-(D72-K)") (class "Default")
      (node (ref "D72") (pin "2") (pinfunction "K_2") (pintype "passive"))
      (node (ref "U4") (pin "30") (pinfunction "S22_30") (pintype "passive"))
    )
    (net (code "89") (name "Net-(D73-K)") (class "Default")
      (node (ref "D73") (pin "2") (pinfunction "K_2") (pintype "passive"))
      (node (ref "U5") (pin "47") (pinfunction "S14_47") (pintype "passive"))
    )
    (net (code "90") (name "Net-(D74-K)") (class "Default")
      (node (ref "D74") (pin "2") (pinfunction "K_2") (pintype "passive"))
      (node (ref "U5") (pin "2") (pinfunction "S11_2") (pintype "passive"))
    )
    (net (code "91") (name "Net-(D75-K)") (class "Default")
      (node (ref "D75") (pin "2") (pinfunction "K_2") (pintype "passive"))
      (node (ref "U5") (pin "6") (pinfunction "S7_6") (pintype "passive"))
    )
    (net (code "92") (name "Net-(D76-K)") (class "Default")
      (node (ref "D76") (pin "2") (pinfunction "K_2") (pintype "passive"))
      (node (ref "U5") (pin "10") (pinfunction "S3_10") (pintype "passive"))
    )
    (net (code "93") (name "Net-(D77-K)") (class "Default")
      (node (ref "D77") (pin "2") (pinfunction "K_2") (pintype "passive"))
      (node (ref "U5") (pin "39") (pinfunction "S31_39") (pintype "passive"))
    )
    (net (code "94") (name "Net-(D78-K)") (class "Default")
      (node (ref "D78") (pin "2") (pinfunction "K_2") (pintype "passive"))
      (node (ref "U5") (pin "35") (pinfunction "S27_35") (pintype "passive"))
    )
    (net (code "95") (name "Net-(D79-K)") (class "Default")
      (node (ref "D79") (pin "2") (pinfunction "K_2") (pintype "passive"))
      (node (ref "U5") (pin "31") (pinfunction "S23_31") (pintype "passive"))
    )
    (net (code "96") (name "Net-(D80-K)") (class "Default")
      (node (ref "D80") (pin "2") (pinfunction "K_2") (pintype "passive"))
      (node (ref "U5") (pin "27") (pinfunction "S19_27") (pintype "passive"))
    )
    (net (code "97") (name "Net-(D81-K)") (class "Default")
      (node (ref "D81") (pin "2") (pinfunction "K_2") (pintype "passive"))
      (node (ref "U4") (pin "47") (pinfunction "S14_47") (pintype "passive"))
    )
    (net (code "98") (name "Net-(D82-K)") (class "Default")
      (node (ref "D82") (pin "2") (pinfunction "K_2") (pintype "passive"))
      (node (ref "U4") (pin "39") (pinfunction "S31_39") (pintype "passive"))
    )
    (net (code "99") (name "Net-(D83-K)") (class "Default")
      (node (ref "D83") (pin "2") (pinfunction "K_2") (pintype "passive"))
      (node (ref "U4") (pin "35") (pinfunction "S27_35") (pintype "passive"))
    )
    (net (code "100") (name "Net-(D84-K)") (class "Default")
      (node (ref "D84") (pin "2") (pinfunction "K_2") (pintype "passive"))
      (node (ref "U4") (pin "31") (pinfunction "S23_31") (pintype "passive"))
    )
    (net (code "101") (name "Net-(D85-K)") (class "Default")
      (node (ref "D85") (pin "2") (pinfunction "K_2") (pintype "passive"))
      (node (ref "U5") (pin "48") (pinfunction "S13_48") (pintype "passive"))
    )
    (net (code "102") (name "Net-(D86-K)") (class "Default")
      (node (ref "D86") (pin "2") (pinfunction "K_2") (pintype "passive"))
      (node (ref "U5") (pin "1") (pinfunction "S12_1") (pintype "passive"))
    )
    (net (code "103") (name "Net-(D87-K)") (class "Default")
      (node (ref "D87") (pin "2") (pinfunction "K_2") (pintype "passive"))
      (node (ref "U5") (pin "5") (pinfunction "S8_5") (pintype "passive"))
    )
    (net (code "104") (name "Net-(D88-K)") (class "Default")
      (node (ref "D88") (pin "2") (pinfunction "K_2") (pintype "passive"))
      (node (ref "U5") (pin "9") (pinfunction "S4_9") (pintype "passive"))
    )
    (net (code "105") (name "Net-(D89-K)") (class "Default")
      (node (ref "D89") (pin "2") (pinfunction "K_2") (pintype "passive"))
      (node (ref "U5") (pin "40") (pinfunction "S32_40") (pintype "passive"))
    )
    (net (code "106") (name "Net-(D90-K)") (class "Default")
      (node (ref "D90") (pin "2") (pinfunction "K_2") (pintype "passive"))
      (node (ref "U5") (pin "36") (pinfunction "S28_36") (pintype "passive"))
    )
    (net (code "107") (name "Net-(D91-K)") (class "Default")
      (node (ref "D91") (pin "2") (pinfunction "K_2") (pintype "passive"))
      (node (ref "U5") (pin "32") (pinfunction "S24_32") (pintype "passive"))
    )
    (net (code "108") (name "Net-(D92-K)") (class "Default")
      (node (ref "D92") (pin "2") (pinfunction "K_2") (pintype "passive"))
      (node (ref "U5") (pin "28") (pinfunction "S20_28") (pintype "passive"))
    )
    (net (code "109") (name "Net-(D93-K)") (class "Default")
      (node (ref "D93") (pin "2") (pinfunction "K_2") (pintype "passive"))
      (node (ref "U4") (pin "48") (pinfunction "S13_48") (pintype "passive"))
    )
    (net (code "110") (name "Net-(D94-K)") (class "Default")
      (node (ref "D94") (pin "2") (pinfunction "K_2") (pintype "passive"))
      (node (ref "U4") (pin "40") (pinfunction "S32_40") (pintype "passive"))
    )
    (net (code "111") (name "Net-(D95-K)") (class "Default")
      (node (ref "D95") (pin "2") (pinfunction "K_2") (pintype "passive"))
      (node (ref "U4") (pin "36") (pinfunction "S28_36") (pintype "passive"))
    )
    (net (code "112") (name "Net-(D96-K)") (class "Default")
      (node (ref "D96") (pin "2") (pinfunction "K_2") (pintype "passive"))
      (node (ref "U4") (pin "32") (pinfunction "S24_32") (pintype "passive"))
    )
    (net (code "113") (name "Net-(U3-IN+)") (class "Default")
      (node (ref "R100") (pin "1") (pinfunction "1_1") (pintype "passive"))
      (node (ref "R101") (pin "2") (pinfunction "2_2") (pintype "passive"))
      (node (ref "U3") (pin "3") (pinfunction "IN+_3") (pintype "input"))
    )
  )
)
